# driver.net
KiCad netlist of a schematic drawn in Altium Designer
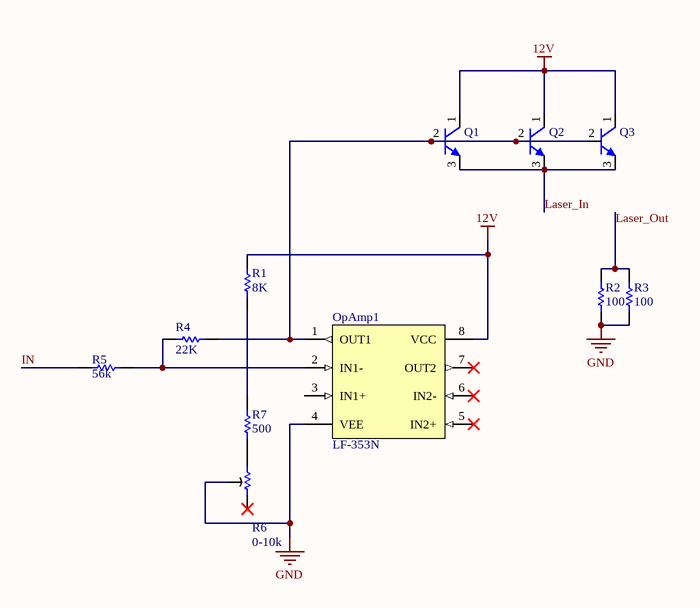
[diagram p0: driver.SchDoc]

(export (version "E")
  (design (tool "Eeschema 10.0.6"))
  (components
    (comp (ref "OpAmp1")
      (value "LF-353N")
      (footprint "6 pin socket")
      (libsource (lib "OpAmps") (part "LF353NFS-ND"))
    )
    (comp (ref "Q1")
      (value "~")
      (footprint "NPN socket")
      (description "NPN Bipolar Transistor")
      (libsource (lib "Transistor") (part "MMBT3904"))
    )
    (comp (ref "Q2")
      (value "~")
      (footprint "NPN socket")
      (description "NPN Bipolar Transistor")
      (libsource (lib "Transistor") (part "MMBT3904"))
    )
    (comp (ref "Q3")
      (value "~")
      (footprint "NPN socket")
      (description "NPN Bipolar Transistor")
      (libsource (lib "Transistor") (part "MMBT3904"))
    )
    (comp (ref "R1")
      (value "8K")
      (footprint "SMT 0805 (2012)")
      (description "Resistor 22K 1% Surface Mount 0804")
      (fields (field (name "POWER") "100 mW") (field (name "Comment") "Resistor 22K 0804"))
      (libsource (lib "Resistor") (part "Resistor 22K 0804"))
    )
    (comp (ref "R2")
      (value "100")
      (footprint "SMT 0805 (2012)")
      (description "Resistor 22K 1% Surface Mount 0804")
      (fields (field (name "POWER") "100 mW") (field (name "Comment") "Resistor 22K 0804"))
      (libsource (lib "Resistor") (part "Resistor 22K 0804"))
    )
    (comp (ref "R3")
      (value "100")
      (footprint "SMT 0805 (2012)")
      (description "Resistor 22K 1% Surface Mount 0804")
      (fields (field (name "POWER") "100 mW") (field (name "Comment") "Resistor 22K 0804"))
      (libsource (lib "Resistor") (part "Resistor 22K 0804"))
    )
    (comp (ref "R4")
      (value "22K")
      (footprint "SMT 0805 (2012)")
      (description "Resistor 22K 1% Surface Mount 0804")
      (fields (field (name "POWER") "100 mW") (field (name "Comment") "Resistor 22K 0804"))
      (libsource (lib "Resistor") (part "Resistor 22K 0804"))
    )
    (comp (ref "R5")
      (value "56k")
      (footprint "SMT 0805 (2012)")
      (description "Resistor 56K 0804")
      (fields (field (name "Comment") "Resistor 56K Ohm"))
      (libsource (lib "Resistor") (part "Resistor 56k Ohm 0804"))
    )
    (comp (ref "R6")
      (value "0-10k")
      (footprint "pot socket")
      (description "10K pot")
      (fields (field (name "POWER") "100 mW"))
      (libsource (lib "Resistor") (part "10K pot"))
    )
    (comp (ref "R7")
      (value "500")
      (footprint "SMT 0805 (2012)")
      (description "Resistor 22K 1% Surface Mount 0804")
      (fields (field (name "POWER") "100 mW") (field (name "Comment") "Resistor 500 0804"))
      (libsource (lib "Resistor") (part "Resistor 22K 0804"))
    )
  )
  (nets
    (net (code "1") (name "/IN") (class "Default")
      (node (ref "R5") (pin "2") (pinfunction "2_2") (pintype "passive"))
    )
    (net (code "2") (name "/Laser_In") (class "Default")
      (node (ref "Q1") (pin "3") (pinfunction "3_3") (pintype "passive"))
      (node (ref "Q2") (pin "3") (pinfunction "3_3") (pintype "passive"))
      (node (ref "Q3") (pin "3") (pinfunction "3_3") (pintype "passive"))
    )
    (net (code "3") (name "/Laser_Out") (class "Default")
      (node (ref "R2") (pin "1") (pinfunction "1_1") (pintype "passive"))
      (node (ref "R3") (pin "1") (pinfunction "1_1") (pintype "passive"))
    )
    (net (code "4") (name "12V") (class "Default")
      (node (ref "OpAmp1") (pin "8") (pinfunction "VCC_8") (pintype "power_in"))
      (node (ref "Q1") (pin "1") (pinfunction "1_1") (pintype "passive"))
      (node (ref "Q2") (pin "1") (pinfunction "1_1") (pintype "passive"))
      (node (ref "Q3") (pin "1") (pinfunction "1_1") (pintype "passive"))
      (node (ref "R1") (pin "1") (pinfunction "1_1") (pintype "passive"))
    )
    (net (code "5") (name "GND") (class "Default")
      (node (ref "OpAmp1") (pin "4") (pinfunction "VEE_4") (pintype "power_in"))
      (node (ref "R2") (pin "2") (pinfunction "2_2") (pintype "passive"))
      (node (ref "R3") (pin "2") (pinfunction "2_2") (pintype "passive"))
      (node (ref "R6") (pin "2") (pinfunction "2_2") (pintype "passive"))
    )
    (net (code "6") (name "Net-(OpAmp1-IN1-)") (class "Default")
      (node (ref "OpAmp1") (pin "2") (pinfunction "IN1-_2") (pintype "input"))
      (node (ref "R4") (pin "1") (pinfunction "1_1") (pintype "passive"))
      (node (ref "R5") (pin "1") (pinfunction "1_1") (pintype "passive"))
    )
    (net (code "7") (name "Net-(OpAmp1-OUT1)") (class "Default")
      (node (ref "OpAmp1") (pin "1") (pinfunction "OUT1_1") (pintype "output"))
      (node (ref "Q1") (pin "2") (pinfunction "2_2") (pintype "passive"))
      (node (ref "Q2") (pin "2") (pinfunction "2_2") (pintype "passive"))
      (node (ref "Q3") (pin "2") (pinfunction "2_2") (pintype "passive"))
      (node (ref "R4") (pin "2") (pinfunction "2_2") (pintype "passive"))
    )
    (net (code "8") (name "Net-(R1-Pad2)") (class "Default")
      (node (ref "R1") (pin "2") (pinfunction "2_2") (pintype "passive"))
      (node (ref "R7") (pin "1") (pinfunction "1_1") (pintype "passive"))
    )
    (net (code "9") (name "Net-(R6-Pad1)") (class "Default")
      (node (ref "R6") (pin "1") (pinfunction "1_1") (pintype "passive"))
      (node (ref "R7") (pin "2") (pinfunction "2_2") (pintype "passive"))
    )
    (net (code "10") (name "unconnected-(OpAmp1-IN1+-Pad3)") (class "Default")
      (node (ref "OpAmp1") (pin "3") (pinfunction "IN1+_3") (pintype "input"))
    )
    (net (code "11") (name "unconnected-(OpAmp1-IN2+-Pad5)") (class "Default")
      (node (ref "OpAmp1") (pin "5") (pinfunction "IN2+_5") (pintype "input+no_connect"))
    )
    (net (code "12") (name "unconnected-(OpAmp1-IN2--Pad6)") (class "Default")
      (node (ref "OpAmp1") (pin "6") (pinfunction "IN2-_6") (pintype "input+no_connect"))
    )
    (net (code "13") (name "unconnected-(OpAmp1-OUT2-Pad7)") (class "Default")
      (node (ref "OpAmp1") (pin "7") (pinfunction "OUT2_7") (pintype "output+no_connect"))
    )
    (net (code "14") (name "unconnected-(R6-Pad3)") (class "Default")
      (node (ref "R6") (pin "3") (pinfunction "3_3") (pintype "passive+no_connect"))
    )
  )
)
